# coin_acceptor.net
KiCad netlist of a schematic drawn in EAGLE
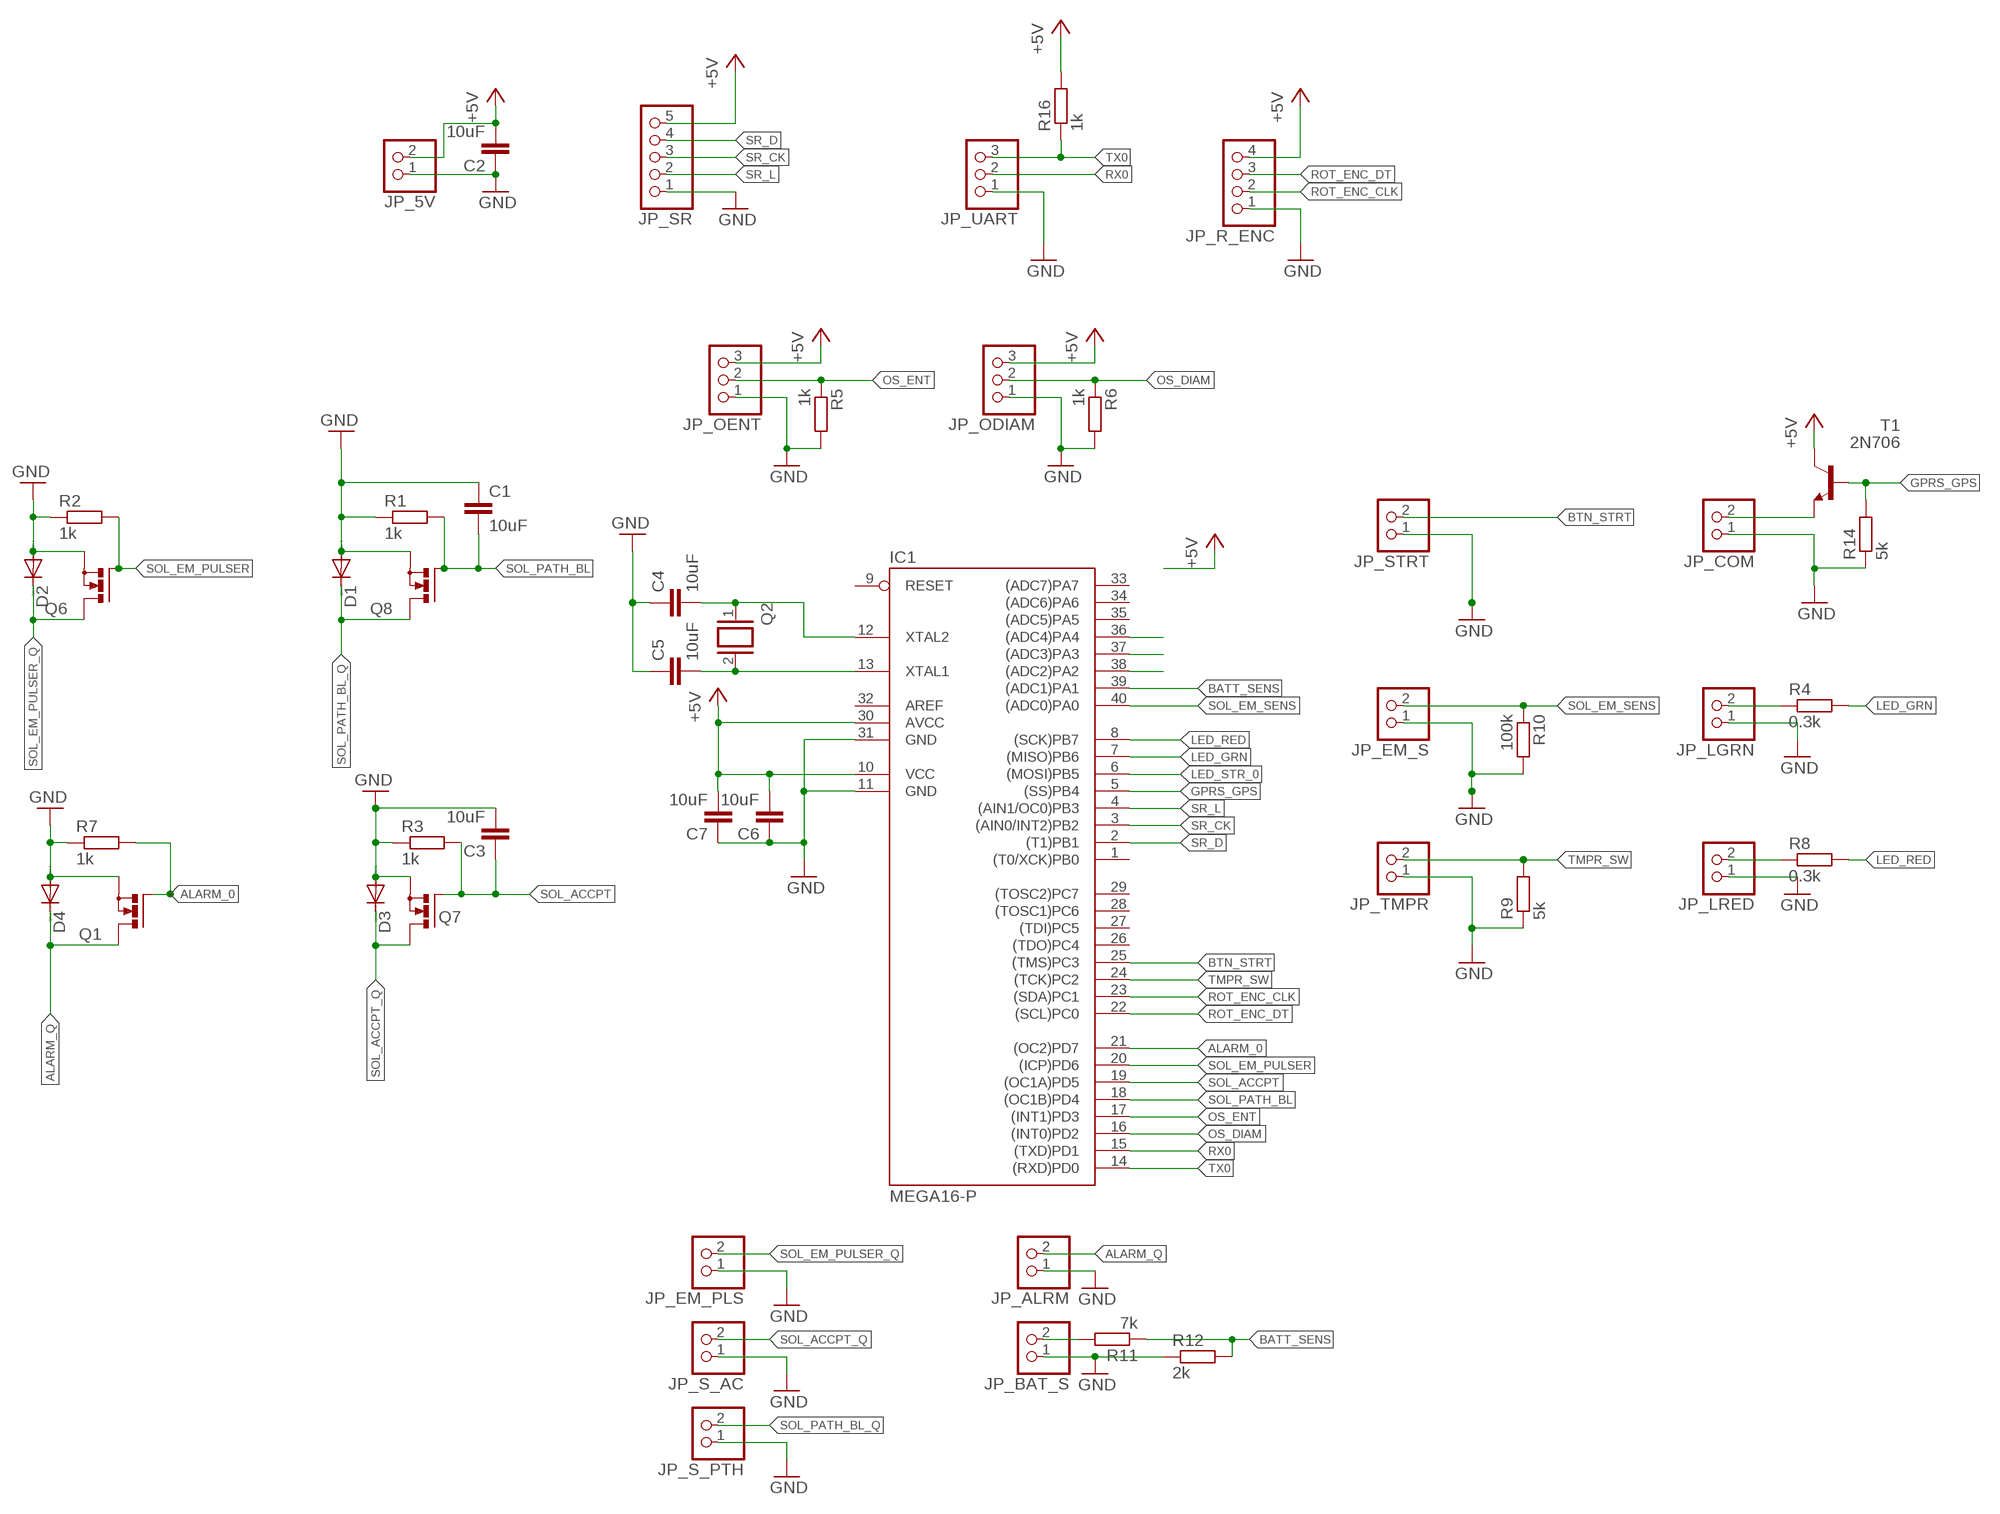
[diagram p0: schematic, sheet 1]

(export (version "E")
  (design (tool "Eeschema 10.0.6"))
  (components
    (comp (ref "C1")
      (value "10uF")
      (footprint "eagle-import:C025-024X044")
      (libsource (lib "eagle-import") (part "C-EU025-024X044"))
    )
    (comp (ref "C2")
      (value "10uF")
      (footprint "eagle-import:C025-024X044")
      (libsource (lib "eagle-import") (part "C-EU025-024X044"))
    )
    (comp (ref "C3")
      (value "10uF")
      (footprint "eagle-import:C025-024X044")
      (libsource (lib "eagle-import") (part "C-EU025-024X044"))
    )
    (comp (ref "C4")
      (value "10uF")
      (footprint "eagle-import:C025-024X044")
      (libsource (lib "eagle-import") (part "C-EU025-024X044"))
    )
    (comp (ref "C5")
      (value "10uF")
      (footprint "eagle-import:C025-024X044")
      (libsource (lib "eagle-import") (part "C-EU025-024X044"))
    )
    (comp (ref "C6")
      (value "10uF")
      (footprint "eagle-import:C025-024X044")
      (libsource (lib "eagle-import") (part "C-EU025-024X044"))
    )
    (comp (ref "C7")
      (value "10uF")
      (footprint "eagle-import:C025-024X044")
      (libsource (lib "eagle-import") (part "C-EU025-024X044"))
    )
    (comp (ref "D1")
      (value "DIODE-DO35-10")
      (footprint "eagle-import:DO35-10")
      (libsource (lib "eagle-import") (part "DIODE-DO35-10"))
    )
    (comp (ref "D2")
      (value "DIODE-DO35-10")
      (footprint "eagle-import:DO35-10")
      (libsource (lib "eagle-import") (part "DIODE-DO35-10"))
    )
    (comp (ref "D3")
      (value "DIODE-DO35-10")
      (footprint "eagle-import:DO35-10")
      (libsource (lib "eagle-import") (part "DIODE-DO35-10"))
    )
    (comp (ref "D4")
      (value "DIODE-DO35-10")
      (footprint "eagle-import:DO35-10")
      (libsource (lib "eagle-import") (part "DIODE-DO35-10"))
    )
    (comp (ref "IC1")
      (value "MEGA16-P")
      (footprint "eagle-import:DIL40")
      (fields (field (name "MPN") "ATMEGA16-16PU"))
      (libsource (lib "eagle-import") (part "MEGA16-P"))
    )
    (comp (ref "JP_5V")
      (value "PINHD-1X2")
      (footprint "eagle-import:1X02")
      (libsource (lib "eagle-import") (part "PINHD-1X2"))
    )
    (comp (ref "JP_ALRM")
      (value "PINHD-1X2")
      (footprint "eagle-import:1X02")
      (libsource (lib "eagle-import") (part "PINHD-1X2"))
    )
    (comp (ref "JP_BAT_S")
      (value "PINHD-1X2")
      (footprint "eagle-import:1X02")
      (libsource (lib "eagle-import") (part "PINHD-1X2"))
    )
    (comp (ref "JP_COM")
      (value "PINHD-1X2")
      (footprint "eagle-import:1X02")
      (libsource (lib "eagle-import") (part "PINHD-1X2"))
    )
    (comp (ref "JP_EM_PLS")
      (value "PINHD-1X2")
      (footprint "eagle-import:1X02")
      (libsource (lib "eagle-import") (part "PINHD-1X2"))
    )
    (comp (ref "JP_EM_S")
      (value "PINHD-1X2")
      (footprint "eagle-import:1X02")
      (libsource (lib "eagle-import") (part "PINHD-1X2"))
    )
    (comp (ref "JP_LGRN")
      (value "PINHD-1X2")
      (footprint "eagle-import:1X02")
      (libsource (lib "eagle-import") (part "PINHD-1X2"))
    )
    (comp (ref "JP_LRED")
      (value "PINHD-1X2")
      (footprint "eagle-import:1X02")
      (libsource (lib "eagle-import") (part "PINHD-1X2"))
    )
    (comp (ref "JP_ODIAM")
      (value "PINHD-1X3")
      (footprint "eagle-import:1X03")
      (libsource (lib "eagle-import") (part "PINHD-1X3"))
    )
    (comp (ref "JP_OENT")
      (value "PINHD-1X3")
      (footprint "eagle-import:1X03")
      (libsource (lib "eagle-import") (part "PINHD-1X3"))
    )
    (comp (ref "JP_R_ENC")
      (value "PINHD-1X4")
      (footprint "eagle-import:1X04")
      (libsource (lib "eagle-import") (part "PINHD-1X4"))
    )
    (comp (ref "JP_SR")
      (value "PINHD-1X5")
      (footprint "eagle-import:1X05")
      (libsource (lib "eagle-import") (part "PINHD-1X5"))
    )
    (comp (ref "JP_STRT")
      (value "PINHD-1X2")
      (footprint "eagle-import:1X02")
      (libsource (lib "eagle-import") (part "PINHD-1X2"))
    )
    (comp (ref "JP_S_AC")
      (value "PINHD-1X2")
      (footprint "eagle-import:1X02")
      (libsource (lib "eagle-import") (part "PINHD-1X2"))
    )
    (comp (ref "JP_S_PTH")
      (value "PINHD-1X2")
      (footprint "eagle-import:1X02")
      (libsource (lib "eagle-import") (part "PINHD-1X2"))
    )
    (comp (ref "JP_TMPR")
      (value "PINHD-1X2")
      (footprint "eagle-import:1X02")
      (libsource (lib "eagle-import") (part "PINHD-1X2"))
    )
    (comp (ref "JP_UART")
      (value "PINHD-1X3")
      (footprint "eagle-import:1X03")
      (libsource (lib "eagle-import") (part "PINHD-1X3"))
    )
    (comp (ref "Q1")
      (value "IRF512")
      (footprint "eagle-import:TO220BV")
      (libsource (lib "eagle-import") (part "IRF512"))
    )
    (comp (ref "Q2")
      (value "XTAL")
      (footprint "eagle-import:Q")
      (libsource (lib "eagle-import") (part "XTAL"))
    )
    (comp (ref "Q6")
      (value "IRF512")
      (footprint "eagle-import:TO220BV")
      (libsource (lib "eagle-import") (part "IRF512"))
    )
    (comp (ref "Q7")
      (value "IRF512")
      (footprint "eagle-import:TO220BV")
      (libsource (lib "eagle-import") (part "IRF512"))
    )
    (comp (ref "Q8")
      (value "IRF512")
      (footprint "eagle-import:TO220BV")
      (libsource (lib "eagle-import") (part "IRF512"))
    )
    (comp (ref "R1")
      (value "1k")
      (footprint "eagle-import:0309_10")
      (libsource (lib "eagle-import") (part "R-EU_0309/10"))
    )
    (comp (ref "R2")
      (value "1k")
      (footprint "eagle-import:0309_10")
      (libsource (lib "eagle-import") (part "R-EU_0309/10"))
    )
    (comp (ref "R3")
      (value "1k")
      (footprint "eagle-import:0309_10")
      (libsource (lib "eagle-import") (part "R-EU_0309/10"))
    )
    (comp (ref "R4")
      (value "0.3k")
      (footprint "eagle-import:0309_10")
      (libsource (lib "eagle-import") (part "R-EU_0309/10"))
    )
    (comp (ref "R5")
      (value "1k")
      (footprint "eagle-import:0309_10")
      (libsource (lib "eagle-import") (part "R-EU_0309/10"))
    )
    (comp (ref "R6")
      (value "1k")
      (footprint "eagle-import:0309_10")
      (libsource (lib "eagle-import") (part "R-EU_0309/10"))
    )
    (comp (ref "R7")
      (value "1k")
      (footprint "eagle-import:0309_10")
      (libsource (lib "eagle-import") (part "R-EU_0309/10"))
    )
    (comp (ref "R8")
      (value "0.3k")
      (footprint "eagle-import:0309_10")
      (libsource (lib "eagle-import") (part "R-EU_0309/10"))
    )
    (comp (ref "R9")
      (value "5k")
      (footprint "eagle-import:0309_10")
      (libsource (lib "eagle-import") (part "R-EU_0309/10"))
    )
    (comp (ref "R10")
      (value "100k")
      (footprint "eagle-import:0309_10")
      (libsource (lib "eagle-import") (part "R-EU_0309/10"))
    )
    (comp (ref "R11")
      (value "7k")
      (footprint "eagle-import:0309_10")
      (libsource (lib "eagle-import") (part "R-EU_0309/10"))
    )
    (comp (ref "R12")
      (value "2k")
      (footprint "eagle-import:0309_10")
      (libsource (lib "eagle-import") (part "R-EU_0309/10"))
    )
    (comp (ref "R14")
      (value "5k")
      (footprint "eagle-import:0309_10")
      (libsource (lib "eagle-import") (part "R-EU_0309/10"))
    )
    (comp (ref "R16")
      (value "1k")
      (footprint "eagle-import:0309_10")
      (libsource (lib "eagle-import") (part "R-EU_0309/10"))
    )
    (comp (ref "T1")
      (value "2N706")
      (footprint "eagle-import:TO18")
      (libsource (lib "eagle-import") (part "2N706"))
    )
  )
  (nets
    (net (code "1") (name "+5V") (class "Default")
      (node (ref "C2") (pin "2") (pinfunction "2_2") (pintype "passive"))
      (node (ref "C6") (pin "2") (pinfunction "2_2") (pintype "passive"))
      (node (ref "C7") (pin "2") (pinfunction "2_2") (pintype "passive"))
      (node (ref "IC1") (pin "10") (pinfunction "VCC_10") (pintype "power_in"))
      (node (ref "IC1") (pin "30") (pinfunction "AVCC_30") (pintype "power_in"))
      (node (ref "JP_5V") (pin "2") (pinfunction "2_2") (pintype "passive"))
      (node (ref "JP_ODIAM") (pin "3") (pinfunction "3_3") (pintype "passive"))
      (node (ref "JP_OENT") (pin "3") (pinfunction "3_3") (pintype "passive"))
      (node (ref "JP_R_ENC") (pin "4") (pinfunction "4_4") (pintype "passive"))
      (node (ref "JP_SR") (pin "5") (pinfunction "5_5") (pintype "passive"))
      (node (ref "R16") (pin "2") (pinfunction "2_2") (pintype "passive"))
      (node (ref "T1") (pin "3") (pinfunction "C_3") (pintype "passive"))
    )
    (net (code "2") (name "ALARM_0") (class "Default")
      (node (ref "IC1") (pin "21") (pinfunction "(OC2)PD7_21") (pintype "bidirectional"))
      (node (ref "Q1") (pin "G") (pinfunction "G_G") (pintype "passive"))
      (node (ref "R7") (pin "2") (pinfunction "2_2") (pintype "passive"))
    )
    (net (code "3") (name "ALARM_Q") (class "Default")
      (node (ref "D4") (pin "C") (pinfunction "C_C") (pintype "passive"))
      (node (ref "JP_ALRM") (pin "2") (pinfunction "2_2") (pintype "passive"))
      (node (ref "Q1") (pin "D") (pinfunction "D_D") (pintype "passive"))
    )
    (net (code "4") (name "BATT_SENS") (class "Default")
      (node (ref "IC1") (pin "39") (pinfunction "(ADC1)PA1_39") (pintype "bidirectional"))
      (node (ref "R11") (pin "1") (pinfunction "1_1") (pintype "passive"))
      (node (ref "R12") (pin "2") (pinfunction "2_2") (pintype "passive"))
    )
    (net (code "5") (name "BTN_STRT") (class "Default")
      (node (ref "IC1") (pin "25") (pinfunction "(TMS)PC3_25") (pintype "bidirectional"))
      (node (ref "JP_STRT") (pin "2") (pinfunction "2_2") (pintype "passive"))
    )
    (net (code "6") (name "GND") (class "Default")
      (node (ref "C1") (pin "1") (pinfunction "1_1") (pintype "passive"))
      (node (ref "C2") (pin "1") (pinfunction "1_1") (pintype "passive"))
      (node (ref "C3") (pin "2") (pinfunction "2_2") (pintype "passive"))
      (node (ref "C4") (pin "1") (pinfunction "1_1") (pintype "passive"))
      (node (ref "C5") (pin "1") (pinfunction "1_1") (pintype "passive"))
      (node (ref "C6") (pin "1") (pinfunction "1_1") (pintype "passive"))
      (node (ref "C7") (pin "1") (pinfunction "1_1") (pintype "passive"))
      (node (ref "D1") (pin "A") (pinfunction "A_A") (pintype "passive"))
      (node (ref "D2") (pin "A") (pinfunction "A_A") (pintype "passive"))
      (node (ref "D3") (pin "A") (pinfunction "A_A") (pintype "passive"))
      (node (ref "D4") (pin "A") (pinfunction "A_A") (pintype "passive"))
      (node (ref "IC1") (pin "11") (pinfunction "GND_11") (pintype "power_in"))
      (node (ref "IC1") (pin "31") (pinfunction "GND_31") (pintype "power_in"))
      (node (ref "JP_5V") (pin "1") (pinfunction "1_1") (pintype "passive"))
      (node (ref "JP_ALRM") (pin "1") (pinfunction "1_1") (pintype "passive"))
      (node (ref "JP_BAT_S") (pin "1") (pinfunction "1_1") (pintype "passive"))
      (node (ref "JP_COM") (pin "1") (pinfunction "1_1") (pintype "passive"))
      (node (ref "JP_EM_PLS") (pin "1") (pinfunction "1_1") (pintype "passive"))
      (node (ref "JP_EM_S") (pin "1") (pinfunction "1_1") (pintype "passive"))
      (node (ref "JP_LGRN") (pin "1") (pinfunction "1_1") (pintype "passive"))
      (node (ref "JP_LRED") (pin "1") (pinfunction "1_1") (pintype "passive"))
      (node (ref "JP_ODIAM") (pin "1") (pinfunction "1_1") (pintype "passive"))
      (node (ref "JP_OENT") (pin "1") (pinfunction "1_1") (pintype "passive"))
      (node (ref "JP_R_ENC") (pin "1") (pinfunction "1_1") (pintype "passive"))
      (node (ref "JP_SR") (pin "1") (pinfunction "1_1") (pintype "passive"))
      (node (ref "JP_STRT") (pin "1") (pinfunction "1_1") (pintype "passive"))
      (node (ref "JP_S_AC") (pin "1") (pinfunction "1_1") (pintype "passive"))
      (node (ref "JP_S_PTH") (pin "1") (pinfunction "1_1") (pintype "passive"))
      (node (ref "JP_TMPR") (pin "1") (pinfunction "1_1") (pintype "passive"))
      (node (ref "JP_UART") (pin "1") (pinfunction "1_1") (pintype "passive"))
      (node (ref "Q1") (pin "S") (pinfunction "S_S") (pintype "passive"))
      (node (ref "Q6") (pin "S") (pinfunction "S_S") (pintype "passive"))
      (node (ref "Q7") (pin "S") (pinfunction "S_S") (pintype "passive"))
      (node (ref "Q8") (pin "S") (pinfunction "S_S") (pintype "passive"))
      (node (ref "R1") (pin "1") (pinfunction "1_1") (pintype "passive"))
      (node (ref "R10") (pin "2") (pinfunction "2_2") (pintype "passive"))
      (node (ref "R12") (pin "1") (pinfunction "1_1") (pintype "passive"))
      (node (ref "R14") (pin "1") (pinfunction "1_1") (pintype "passive"))
      (node (ref "R2") (pin "1") (pinfunction "1_1") (pintype "passive"))
      (node (ref "R3") (pin "1") (pinfunction "1_1") (pintype "passive"))
      (node (ref "R5") (pin "2") (pinfunction "2_2") (pintype "passive"))
      (node (ref "R6") (pin "2") (pinfunction "2_2") (pintype "passive"))
      (node (ref "R7") (pin "1") (pinfunction "1_1") (pintype "passive"))
      (node (ref "R9") (pin "1") (pinfunction "1_1") (pintype "passive"))
    )
    (net (code "7") (name "GPRS_GPS") (class "Default")
      (node (ref "IC1") (pin "5") (pinfunction "(SS)PB4_5") (pintype "bidirectional"))
      (node (ref "R14") (pin "2") (pinfunction "2_2") (pintype "passive"))
      (node (ref "T1") (pin "2") (pinfunction "B_2") (pintype "passive"))
    )
    (net (code "8") (name "LED_GRN") (class "Default")
      (node (ref "IC1") (pin "7") (pinfunction "(MISO)PB6_7") (pintype "bidirectional"))
      (node (ref "R4") (pin "2") (pinfunction "2_2") (pintype "passive"))
    )
    (net (code "9") (name "LED_RED") (class "Default")
      (node (ref "IC1") (pin "8") (pinfunction "(SCK)PB7_8") (pintype "bidirectional"))
      (node (ref "R8") (pin "2") (pinfunction "2_2") (pintype "passive"))
    )
    (net (code "10") (name "LED_STR_0") (class "Default")
      (node (ref "IC1") (pin "6") (pinfunction "(MOSI)PB5_6") (pintype "bidirectional"))
    )
    (net (code "11") (name "Net-(IC1-XTAL1)") (class "Default")
      (node (ref "C5") (pin "2") (pinfunction "2_2") (pintype "passive"))
      (node (ref "IC1") (pin "13") (pinfunction "XTAL1_13") (pintype "bidirectional"))
      (node (ref "Q2") (pin "2") (pinfunction "2_2") (pintype "passive"))
    )
    (net (code "12") (name "Net-(IC1-XTAL2)") (class "Default")
      (node (ref "C4") (pin "2") (pinfunction "2_2") (pintype "passive"))
      (node (ref "IC1") (pin "12") (pinfunction "XTAL2_12") (pintype "bidirectional"))
      (node (ref "Q2") (pin "1") (pinfunction "1_1") (pintype "passive"))
    )
    (net (code "13") (name "Net-(JP_BAT_S-Pad2)") (class "Default")
      (node (ref "JP_BAT_S") (pin "2") (pinfunction "2_2") (pintype "passive"))
      (node (ref "R11") (pin "2") (pinfunction "2_2") (pintype "passive"))
    )
    (net (code "14") (name "Net-(JP_LGRN-Pad2)") (class "Default")
      (node (ref "JP_LGRN") (pin "2") (pinfunction "2_2") (pintype "passive"))
      (node (ref "R4") (pin "1") (pinfunction "1_1") (pintype "passive"))
    )
    (net (code "15") (name "Net-(JP_LRED-Pad2)") (class "Default")
      (node (ref "JP_LRED") (pin "2") (pinfunction "2_2") (pintype "passive"))
      (node (ref "R8") (pin "1") (pinfunction "1_1") (pintype "passive"))
    )
    (net (code "16") (name "Net-(T1-E)") (class "Default")
      (node (ref "JP_COM") (pin "2") (pinfunction "2_2") (pintype "passive"))
      (node (ref "T1") (pin "1") (pinfunction "E_1") (pintype "passive"))
    )
    (net (code "17") (name "OS_DIAM") (class "Default")
      (node (ref "IC1") (pin "16") (pinfunction "(INT0)PD2_16") (pintype "bidirectional"))
      (node (ref "JP_ODIAM") (pin "2") (pinfunction "2_2") (pintype "passive"))
      (node (ref "R6") (pin "1") (pinfunction "1_1") (pintype "passive"))
    )
    (net (code "18") (name "OS_ENT") (class "Default")
      (node (ref "IC1") (pin "17") (pinfunction "(INT1)PD3_17") (pintype "bidirectional"))
      (node (ref "JP_OENT") (pin "2") (pinfunction "2_2") (pintype "passive"))
      (node (ref "R5") (pin "1") (pinfunction "1_1") (pintype "passive"))
    )
    (net (code "19") (name "ROT_ENC_CLK") (class "Default")
      (node (ref "IC1") (pin "23") (pinfunction "(SDA)PC1_23") (pintype "bidirectional"))
      (node (ref "JP_R_ENC") (pin "2") (pinfunction "2_2") (pintype "passive"))
    )
    (net (code "20") (name "ROT_ENC_DT") (class "Default")
      (node (ref "IC1") (pin "22") (pinfunction "(SCL)PC0_22") (pintype "bidirectional"))
      (node (ref "JP_R_ENC") (pin "3") (pinfunction "3_3") (pintype "passive"))
    )
    (net (code "21") (name "RX0") (class "Default")
      (node (ref "IC1") (pin "15") (pinfunction "(TXD)PD1_15") (pintype "bidirectional"))
      (node (ref "JP_UART") (pin "2") (pinfunction "2_2") (pintype "passive"))
    )
    (net (code "22") (name "SOL_ACCPT") (class "Default")
      (node (ref "C3") (pin "1") (pinfunction "1_1") (pintype "passive"))
      (node (ref "IC1") (pin "19") (pinfunction "(OC1A)PD5_19") (pintype "bidirectional"))
      (node (ref "Q7") (pin "G") (pinfunction "G_G") (pintype "passive"))
      (node (ref "R3") (pin "2") (pinfunction "2_2") (pintype "passive"))
    )
    (net (code "23") (name "SOL_ACCPT_Q") (class "Default")
      (node (ref "D3") (pin "C") (pinfunction "C_C") (pintype "passive"))
      (node (ref "JP_S_AC") (pin "2") (pinfunction "2_2") (pintype "passive"))
      (node (ref "Q7") (pin "D") (pinfunction "D_D") (pintype "passive"))
    )
    (net (code "24") (name "SOL_EM_PULSER") (class "Default")
      (node (ref "IC1") (pin "20") (pinfunction "(ICP)PD6_20") (pintype "bidirectional"))
      (node (ref "Q6") (pin "G") (pinfunction "G_G") (pintype "passive"))
      (node (ref "R2") (pin "2") (pinfunction "2_2") (pintype "passive"))
    )
    (net (code "25") (name "SOL_EM_PULSER_Q") (class "Default")
      (node (ref "D2") (pin "C") (pinfunction "C_C") (pintype "passive"))
      (node (ref "JP_EM_PLS") (pin "2") (pinfunction "2_2") (pintype "passive"))
      (node (ref "Q6") (pin "D") (pinfunction "D_D") (pintype "passive"))
    )
    (net (code "26") (name "SOL_EM_SENS") (class "Default")
      (node (ref "IC1") (pin "40") (pinfunction "(ADC0)PA0_40") (pintype "bidirectional"))
      (node (ref "JP_EM_S") (pin "2") (pinfunction "2_2") (pintype "passive"))
      (node (ref "R10") (pin "1") (pinfunction "1_1") (pintype "passive"))
    )
    (net (code "27") (name "SOL_PATH_BL") (class "Default")
      (node (ref "C1") (pin "2") (pinfunction "2_2") (pintype "passive"))
      (node (ref "IC1") (pin "18") (pinfunction "(OC1B)PD4_18") (pintype "bidirectional"))
      (node (ref "Q8") (pin "G") (pinfunction "G_G") (pintype "passive"))
      (node (ref "R1") (pin "2") (pinfunction "2_2") (pintype "passive"))
    )
    (net (code "28") (name "SOL_PATH_BL_Q") (class "Default")
      (node (ref "D1") (pin "C") (pinfunction "C_C") (pintype "passive"))
      (node (ref "JP_S_PTH") (pin "2") (pinfunction "2_2") (pintype "passive"))
      (node (ref "Q8") (pin "D") (pinfunction "D_D") (pintype "passive"))
    )
    (net (code "29") (name "SR_CK") (class "Default")
      (node (ref "IC1") (pin "3") (pinfunction "(AIN0/INT2)PB2_3") (pintype "bidirectional"))
      (node (ref "JP_SR") (pin "3") (pinfunction "3_3") (pintype "passive"))
    )
    (net (code "30") (name "SR_D") (class "Default")
      (node (ref "IC1") (pin "2") (pinfunction "(T1)PB1_2") (pintype "bidirectional"))
      (node (ref "JP_SR") (pin "4") (pinfunction "4_4") (pintype "passive"))
    )
    (net (code "31") (name "SR_L") (class "Default")
      (node (ref "IC1") (pin "4") (pinfunction "(AIN1/OC0)PB3_4") (pintype "bidirectional"))
      (node (ref "JP_SR") (pin "2") (pinfunction "2_2") (pintype "passive"))
    )
    (net (code "32") (name "TMPR_SW") (class "Default")
      (node (ref "IC1") (pin "24") (pinfunction "(TCK)PC2_24") (pintype "bidirectional"))
      (node (ref "JP_TMPR") (pin "2") (pinfunction "2_2") (pintype "passive"))
      (node (ref "R9") (pin "2") (pinfunction "2_2") (pintype "passive"))
    )
    (net (code "33") (name "TX0") (class "Default")
      (node (ref "IC1") (pin "14") (pinfunction "(RXD)PD0_14") (pintype "bidirectional"))
      (node (ref "JP_UART") (pin "3") (pinfunction "3_3") (pintype "passive"))
      (node (ref "R16") (pin "1") (pinfunction "1_1") (pintype "passive"))
    )
    (net (code "34") (name "unconnected-(IC1-(ADC2)PA2-Pad38)") (class "Default")
      (node (ref "IC1") (pin "38") (pinfunction "(ADC2)PA2_38") (pintype "bidirectional"))
    )
    (net (code "35") (name "unconnected-(IC1-(ADC3)PA3-Pad37)") (class "Default")
      (node (ref "IC1") (pin "37") (pinfunction "(ADC3)PA3_37") (pintype "bidirectional"))
    )
    (net (code "36") (name "unconnected-(IC1-(ADC4)PA4-Pad36)") (class "Default")
      (node (ref "IC1") (pin "36") (pinfunction "(ADC4)PA4_36") (pintype "bidirectional"))
    )
    (net (code "37") (name "unconnected-(IC1-(ADC5)PA5-Pad35)") (class "Default")
      (node (ref "IC1") (pin "35") (pinfunction "(ADC5)PA5_35") (pintype "bidirectional"))
    )
    (net (code "38") (name "unconnected-(IC1-(ADC6)PA6-Pad34)") (class "Default")
      (node (ref "IC1") (pin "34") (pinfunction "(ADC6)PA6_34") (pintype "bidirectional"))
    )
    (net (code "39") (name "unconnected-(IC1-(ADC7)PA7-Pad33)") (class "Default")
      (node (ref "IC1") (pin "33") (pinfunction "(ADC7)PA7_33") (pintype "bidirectional"))
    )
    (net (code "40") (name "unconnected-(IC1-(T0{slash}XCK)PB0-Pad1)") (class "Default")
      (node (ref "IC1") (pin "1") (pinfunction "(T0/XCK)PB0_1") (pintype "bidirectional"))
    )
    (net (code "41") (name "unconnected-(IC1-(TDI)PC5-Pad27)") (class "Default")
      (node (ref "IC1") (pin "27") (pinfunction "(TDI)PC5_27") (pintype "bidirectional"))
    )
    (net (code "42") (name "unconnected-(IC1-(TDO)PC4-Pad26)") (class "Default")
      (node (ref "IC1") (pin "26") (pinfunction "(TDO)PC4_26") (pintype "bidirectional"))
    )
    (net (code "43") (name "unconnected-(IC1-(TOSC1)PC6-Pad28)") (class "Default")
      (node (ref "IC1") (pin "28") (pinfunction "(TOSC1)PC6_28") (pintype "bidirectional"))
    )
    (net (code "44") (name "unconnected-(IC1-(TOSC2)PC7-Pad29)") (class "Default")
      (node (ref "IC1") (pin "29") (pinfunction "(TOSC2)PC7_29") (pintype "bidirectional"))
    )
    (net (code "45") (name "unconnected-(IC1-AREF-Pad32)") (class "Default")
      (node (ref "IC1") (pin "32") (pinfunction "AREF_32") (pintype "passive"))
    )
    (net (code "46") (name "unconnected-(IC1-RESET-Pad9)") (class "Default")
      (node (ref "IC1") (pin "9") (pinfunction "RESET_9") (pintype "input"))
    )
  )
)
